# Esp_Board.net
KiCad netlist of a schematic drawn in EAGLE
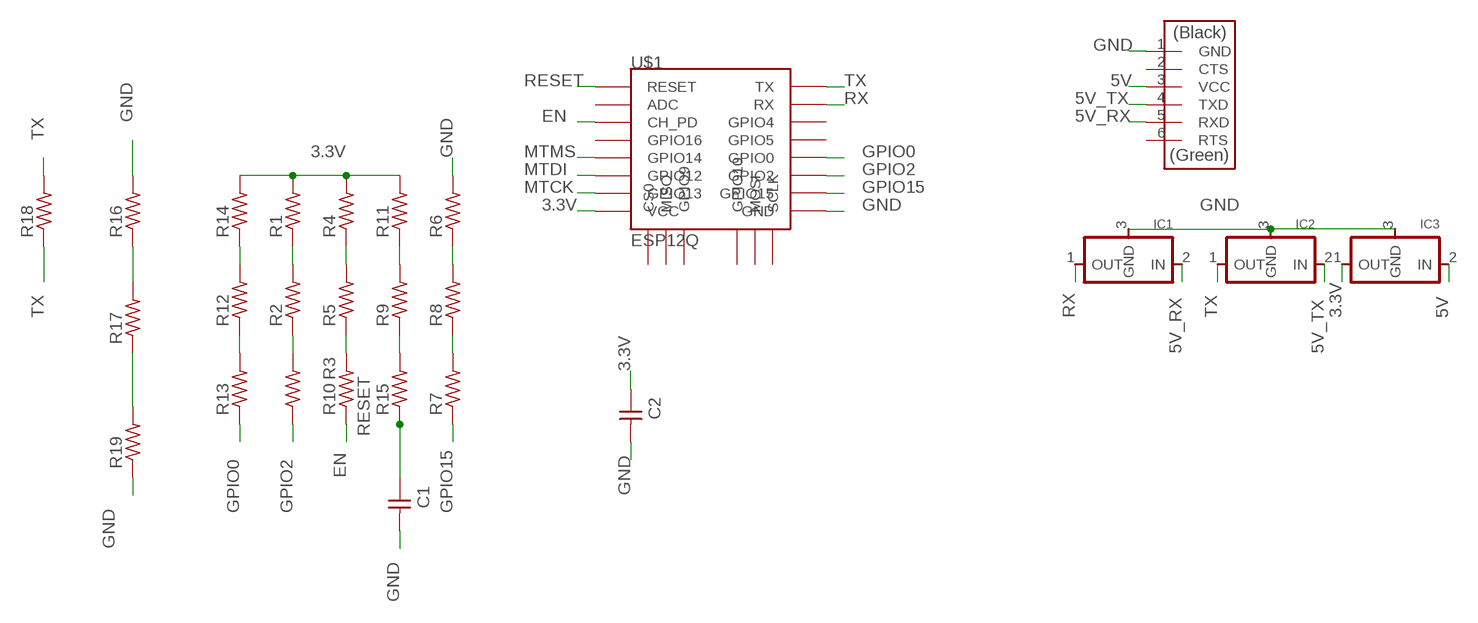
[diagram p0: schematic, sheet 1]

(export (version "E")
  (design (tool "Eeschema 10.0.6"))
  (components
    (comp (ref "C1")
      (value "CAP-UNPOLARIZEDFAB")
      (footprint "eagle-import:C1206FAB")
      (libsource (lib "eagle-import") (part "CAP-UNPOLARIZEDFAB"))
    )
    (comp (ref "C2")
      (value "CAP-UNPOLARIZEDFAB")
      (footprint "eagle-import:C1206FAB")
      (libsource (lib "eagle-import") (part "CAP-UNPOLARIZEDFAB"))
    )
    (comp (ref "IC1")
      (value "REGULATORSOT23")
      (footprint "eagle-import:SOT23")
      (libsource (lib "eagle-import") (part "REGULATORSOT23"))
    )
    (comp (ref "IC2")
      (value "REGULATORSOT23")
      (footprint "eagle-import:SOT23")
      (libsource (lib "eagle-import") (part "REGULATORSOT23"))
    )
    (comp (ref "IC3")
      (value "REGULATORSOT23")
      (footprint "eagle-import:SOT23")
      (libsource (lib "eagle-import") (part "REGULATORSOT23"))
    )
    (comp (ref "R1")
      (value "RES-US1206FAB")
      (footprint "eagle-import:R1206FAB")
      (libsource (lib "eagle-import") (part "RES-US1206FAB"))
    )
    (comp (ref "R2")
      (value "RES-US1206FAB")
      (footprint "eagle-import:R1206FAB")
      (libsource (lib "eagle-import") (part "RES-US1206FAB"))
    )
    (comp (ref "R3")
      (value "RES-US1206FAB")
      (footprint "eagle-import:R1206FAB")
      (libsource (lib "eagle-import") (part "RES-US1206FAB"))
    )
    (comp (ref "R4")
      (value "RES-US1206FAB")
      (footprint "eagle-import:R1206FAB")
      (libsource (lib "eagle-import") (part "RES-US1206FAB"))
    )
    (comp (ref "R5")
      (value "RES-US1206FAB")
      (footprint "eagle-import:R1206FAB")
      (libsource (lib "eagle-import") (part "RES-US1206FAB"))
    )
    (comp (ref "R6")
      (value "RES-US1206FAB")
      (footprint "eagle-import:R1206FAB")
      (libsource (lib "eagle-import") (part "RES-US1206FAB"))
    )
    (comp (ref "R7")
      (value "RES-US1206FAB")
      (footprint "eagle-import:R1206FAB")
      (libsource (lib "eagle-import") (part "RES-US1206FAB"))
    )
    (comp (ref "R8")
      (value "RES-US1206FAB")
      (footprint "eagle-import:R1206FAB")
      (libsource (lib "eagle-import") (part "RES-US1206FAB"))
    )
    (comp (ref "R9")
      (value "RES-US1206FAB")
      (footprint "eagle-import:R1206FAB")
      (libsource (lib "eagle-import") (part "RES-US1206FAB"))
    )
    (comp (ref "R10")
      (value "RES-US1206FAB")
      (footprint "eagle-import:R1206FAB")
      (libsource (lib "eagle-import") (part "RES-US1206FAB"))
    )
    (comp (ref "R11")
      (value "RES-US1206FAB")
      (footprint "eagle-import:R1206FAB")
      (libsource (lib "eagle-import") (part "RES-US1206FAB"))
    )
    (comp (ref "R12")
      (value "RES-US1206FAB")
      (footprint "eagle-import:R1206FAB")
      (libsource (lib "eagle-import") (part "RES-US1206FAB"))
    )
    (comp (ref "R13")
      (value "RES-US1206FAB")
      (footprint "eagle-import:R1206FAB")
      (libsource (lib "eagle-import") (part "RES-US1206FAB"))
    )
    (comp (ref "R14")
      (value "RES-US1206FAB")
      (footprint "eagle-import:R1206FAB")
      (libsource (lib "eagle-import") (part "RES-US1206FAB"))
    )
    (comp (ref "R15")
      (value "RES-US1206FAB")
      (footprint "eagle-import:R1206FAB")
      (libsource (lib "eagle-import") (part "RES-US1206FAB"))
    )
    (comp (ref "R16")
      (value "RES-US1206FAB")
      (footprint "eagle-import:R1206FAB")
      (libsource (lib "eagle-import") (part "RES-US1206FAB"))
    )
    (comp (ref "R17")
      (value "RES-US1206FAB")
      (footprint "eagle-import:R1206FAB")
      (libsource (lib "eagle-import") (part "RES-US1206FAB"))
    )
    (comp (ref "R18")
      (value "RES-US1206FAB")
      (footprint "eagle-import:R1206FAB")
      (libsource (lib "eagle-import") (part "RES-US1206FAB"))
    )
    (comp (ref "R19")
      (value "RES-US1206FAB")
      (footprint "eagle-import:R1206FAB")
      (libsource (lib "eagle-import") (part "RES-US1206FAB"))
    )
    (comp (ref "U$1")
      (value "ESP12Q")
      (footprint "eagle-import:ESP12Q")
      (libsource (lib "eagle-import") (part "ESP12Q"))
    )
    (comp (ref "U$2")
      (value "FTDI-SMD-HEADER")
      (footprint "eagle-import:1X06SMD")
      (libsource (lib "eagle-import") (part "FTDI-SMD-HEADER"))
    )
  )
  (nets
    (net (code "1") (name "/3.3V") (class "Default")
      (node (ref "C2") (pin "1") (pinfunction "1_1") (pintype "passive"))
      (node (ref "IC3") (pin "1") (pinfunction "OUT_1") (pintype "bidirectional"))
      (node (ref "R1") (pin "2") (pinfunction "2_2") (pintype "passive"))
      (node (ref "R11") (pin "2") (pinfunction "2_2") (pintype "passive"))
      (node (ref "R14") (pin "2") (pinfunction "2_2") (pintype "passive"))
      (node (ref "R4") (pin "2") (pinfunction "2_2") (pintype "passive"))
      (node (ref "U$1") (pin "VCC") (pinfunction "VCC_VCC") (pintype "bidirectional"))
    )
    (net (code "2") (name "/5V") (class "Default")
      (node (ref "IC3") (pin "2") (pinfunction "IN_2") (pintype "bidirectional"))
      (node (ref "U$2") (pin "3") (pinfunction "VCC_3") (pintype "bidirectional"))
    )
    (net (code "3") (name "/5V_RX") (class "Default")
      (node (ref "IC1") (pin "2") (pinfunction "IN_2") (pintype "bidirectional"))
      (node (ref "U$2") (pin "5") (pinfunction "RXD_5") (pintype "bidirectional"))
    )
    (net (code "4") (name "/5V_TX") (class "Default")
      (node (ref "IC2") (pin "2") (pinfunction "IN_2") (pintype "bidirectional"))
      (node (ref "U$2") (pin "4") (pinfunction "TXD_4") (pintype "bidirectional"))
    )
    (net (code "5") (name "/EN") (class "Default")
      (node (ref "R10") (pin "1") (pinfunction "1_1") (pintype "passive"))
      (node (ref "U$1") (pin "CH_PD") (pinfunction "CH_PD_CH_PD") (pintype "bidirectional"))
    )
    (net (code "6") (name "/GND") (class "Default")
      (node (ref "C1") (pin "2") (pinfunction "2_2") (pintype "passive"))
      (node (ref "C2") (pin "2") (pinfunction "2_2") (pintype "passive"))
      (node (ref "IC1") (pin "3") (pinfunction "GND_3") (pintype "bidirectional"))
      (node (ref "IC2") (pin "3") (pinfunction "GND_3") (pintype "bidirectional"))
      (node (ref "IC3") (pin "3") (pinfunction "GND_3") (pintype "bidirectional"))
      (node (ref "R16") (pin "1") (pinfunction "1_1") (pintype "passive"))
      (node (ref "R16") (pin "2") (pinfunction "2_2") (pintype "passive"))
      (node (ref "R17") (pin "1") (pinfunction "1_1") (pintype "passive"))
      (node (ref "R17") (pin "2") (pinfunction "2_2") (pintype "passive"))
      (node (ref "R19") (pin "1") (pinfunction "1_1") (pintype "passive"))
      (node (ref "R19") (pin "2") (pinfunction "2_2") (pintype "passive"))
      (node (ref "R6") (pin "2") (pinfunction "2_2") (pintype "passive"))
      (node (ref "U$1") (pin "GND") (pinfunction "GND_GND") (pintype "bidirectional"))
      (node (ref "U$2") (pin "1") (pinfunction "GND_1") (pintype "bidirectional"))
    )
    (net (code "7") (name "/GPIO0") (class "Default")
      (node (ref "R13") (pin "1") (pinfunction "1_1") (pintype "passive"))
      (node (ref "U$1") (pin "GPIO0") (pinfunction "GPIO0_GPIO0") (pintype "bidirectional"))
    )
    (net (code "8") (name "/GPIO2") (class "Default")
      (node (ref "R3") (pin "1") (pinfunction "1_1") (pintype "passive"))
      (node (ref "U$1") (pin "GPIO2") (pinfunction "GPIO2_GPIO2") (pintype "bidirectional"))
    )
    (net (code "9") (name "/GPIO15") (class "Default")
      (node (ref "R7") (pin "1") (pinfunction "1_1") (pintype "passive"))
      (node (ref "U$1") (pin "GPIO15") (pinfunction "GPIO15_GPIO15") (pintype "bidirectional"))
    )
    (net (code "10") (name "/MTCK") (class "Default")
      (node (ref "U$1") (pin "GPIO13") (pinfunction "GPIO13_GPIO13") (pintype "bidirectional"))
    )
    (net (code "11") (name "/MTDI") (class "Default")
      (node (ref "U$1") (pin "GPIO12") (pinfunction "GPIO12_GPIO12") (pintype "bidirectional"))
    )
    (net (code "12") (name "/MTMS") (class "Default")
      (node (ref "U$1") (pin "GPIO14") (pinfunction "GPIO14_GPIO14") (pintype "bidirectional"))
    )
    (net (code "13") (name "/RESET") (class "Default")
      (node (ref "C1") (pin "1") (pinfunction "1_1") (pintype "passive"))
      (node (ref "R15") (pin "1") (pinfunction "1_1") (pintype "passive"))
      (node (ref "U$1") (pin "RESET") (pinfunction "RESET_RESET") (pintype "bidirectional"))
    )
    (net (code "14") (name "/RX") (class "Default")
      (node (ref "IC1") (pin "1") (pinfunction "OUT_1") (pintype "bidirectional"))
      (node (ref "U$1") (pin "RX") (pinfunction "RX_RX") (pintype "bidirectional"))
    )
    (net (code "15") (name "/TX") (class "Default")
      (node (ref "IC2") (pin "1") (pinfunction "OUT_1") (pintype "bidirectional"))
      (node (ref "R18") (pin "1") (pinfunction "1_1") (pintype "passive"))
      (node (ref "R18") (pin "2") (pinfunction "2_2") (pintype "passive"))
      (node (ref "U$1") (pin "TX") (pinfunction "TX_TX") (pintype "bidirectional"))
    )
    (net (code "16") (name "Net-(R1-Pad1)") (class "Default")
      (node (ref "R1") (pin "1") (pinfunction "1_1") (pintype "passive"))
      (node (ref "R2") (pin "2") (pinfunction "2_2") (pintype "passive"))
    )
    (net (code "17") (name "Net-(R2-Pad1)") (class "Default")
      (node (ref "R2") (pin "1") (pinfunction "1_1") (pintype "passive"))
      (node (ref "R3") (pin "2") (pinfunction "2_2") (pintype "passive"))
    )
    (net (code "18") (name "Net-(R4-Pad1)") (class "Default")
      (node (ref "R4") (pin "1") (pinfunction "1_1") (pintype "passive"))
      (node (ref "R5") (pin "2") (pinfunction "2_2") (pintype "passive"))
    )
    (net (code "19") (name "Net-(R6-Pad1)") (class "Default")
      (node (ref "R6") (pin "1") (pinfunction "1_1") (pintype "passive"))
      (node (ref "R8") (pin "2") (pinfunction "2_2") (pintype "passive"))
    )
    (net (code "20") (name "Net-(R7-Pad2)") (class "Default")
      (node (ref "R7") (pin "2") (pinfunction "2_2") (pintype "passive"))
      (node (ref "R8") (pin "1") (pinfunction "1_1") (pintype "passive"))
    )
    (net (code "21") (name "Net-(R10-Pad2)") (class "Default")
      (node (ref "R10") (pin "2") (pinfunction "2_2") (pintype "passive"))
      (node (ref "R5") (pin "1") (pinfunction "1_1") (pintype "passive"))
    )
    (net (code "22") (name "Net-(R11-Pad1)") (class "Default")
      (node (ref "R11") (pin "1") (pinfunction "1_1") (pintype "passive"))
      (node (ref "R9") (pin "2") (pinfunction "2_2") (pintype "passive"))
    )
    (net (code "23") (name "Net-(R12-Pad1)") (class "Default")
      (node (ref "R12") (pin "1") (pinfunction "1_1") (pintype "passive"))
      (node (ref "R13") (pin "2") (pinfunction "2_2") (pintype "passive"))
    )
    (net (code "24") (name "Net-(R12-Pad2)") (class "Default")
      (node (ref "R12") (pin "2") (pinfunction "2_2") (pintype "passive"))
      (node (ref "R14") (pin "1") (pinfunction "1_1") (pintype "passive"))
    )
    (net (code "25") (name "Net-(R15-Pad2)") (class "Default")
      (node (ref "R15") (pin "2") (pinfunction "2_2") (pintype "passive"))
      (node (ref "R9") (pin "1") (pinfunction "1_1") (pintype "passive"))
    )
    (net (code "26") (name "unconnected-(U$1-PadADC)") (class "Default")
      (node (ref "U$1") (pin "ADC") (pinfunction "ADC_ADC") (pintype "bidirectional"))
    )
    (net (code "27") (name "unconnected-(U$1-PadCS0)") (class "Default")
      (node (ref "U$1") (pin "CS0") (pinfunction "CS0_CS0") (pintype "bidirectional"))
    )
    (net (code "28") (name "unconnected-(U$1-PadGPIO4)") (class "Default")
      (node (ref "U$1") (pin "GPIO4") (pinfunction "GPIO4_GPIO4") (pintype "bidirectional"))
    )
    (net (code "29") (name "unconnected-(U$1-PadGPIO5)") (class "Default")
      (node (ref "U$1") (pin "GPIO5") (pinfunction "GPIO5_GPIO5") (pintype "bidirectional"))
    )
    (net (code "30") (name "unconnected-(U$1-PadGPIO9)") (class "Default")
      (node (ref "U$1") (pin "GPIO9") (pinfunction "GPIO9_GPIO9") (pintype "bidirectional"))
    )
    (net (code "31") (name "unconnected-(U$1-PadGPIO10)") (class "Default")
      (node (ref "U$1") (pin "GPIO10") (pinfunction "GPIO10_GPIO10") (pintype "bidirectional"))
    )
    (net (code "32") (name "unconnected-(U$1-PadGPIO16)") (class "Default")
      (node (ref "U$1") (pin "GPIO16") (pinfunction "GPIO16_GPIO16") (pintype "bidirectional"))
    )
    (net (code "33") (name "unconnected-(U$1-PadMISO)") (class "Default")
      (node (ref "U$1") (pin "MISO") (pinfunction "MISO_MISO") (pintype "bidirectional"))
    )
    (net (code "34") (name "unconnected-(U$1-PadMOSI)") (class "Default")
      (node (ref "U$1") (pin "MOSI") (pinfunction "MOSI_MOSI") (pintype "bidirectional"))
    )
    (net (code "35") (name "unconnected-(U$1-PadSCLK)") (class "Default")
      (node (ref "U$1") (pin "SCLK") (pinfunction "SCLK_SCLK") (pintype "bidirectional"))
    )
    (net (code "36") (name "unconnected-(U$2-CTS-Pad2)") (class "Default")
      (node (ref "U$2") (pin "2") (pinfunction "CTS_2") (pintype "bidirectional"))
    )
    (net (code "37") (name "unconnected-(U$2-RTS-Pad6)") (class "Default")
      (node (ref "U$2") (pin "6") (pinfunction "RTS_6") (pintype "bidirectional"))
    )
  )
)
